# tps62180_v0001.net
KiCad netlist of a schematic drawn in EAGLE
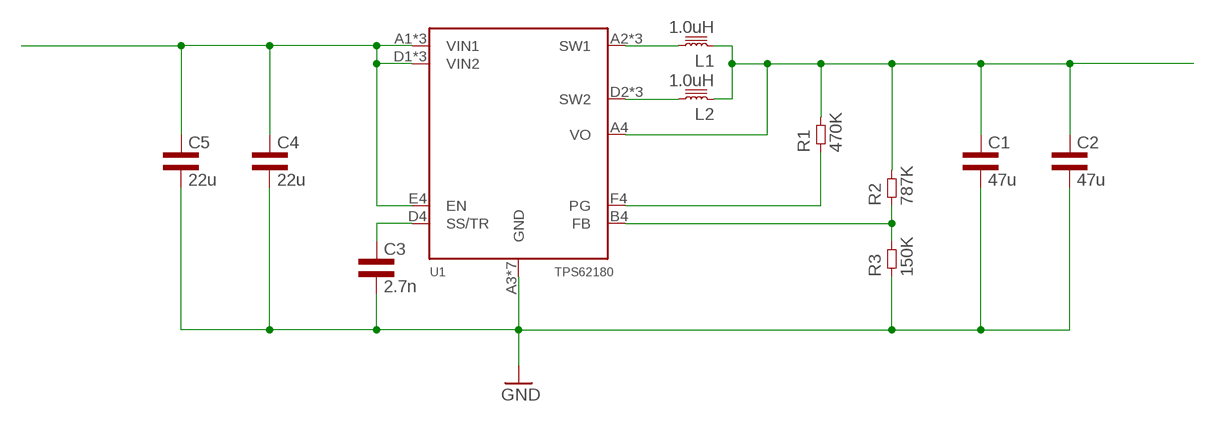
[diagram p0: schematic, sheet 1]

(export (version "E")
  (design (tool "Eeschema 10.0.6"))
  (components
    (comp (ref "C1")
      (value "47u")
      (footprint "eagle-import:1206L3")
      (libsource (lib "eagle-import") (part "CAP1206L3"))
    )
    (comp (ref "C2")
      (value "47u")
      (footprint "eagle-import:1206L3")
      (libsource (lib "eagle-import") (part "CAP1206L3"))
    )
    (comp (ref "C3")
      (value "2.7n")
      (footprint "eagle-import:0402L3")
      (libsource (lib "eagle-import") (part "CAP0402L3"))
    )
    (comp (ref "C4")
      (value "22u")
      (footprint "eagle-import:1206L3")
      (libsource (lib "eagle-import") (part "CAP1206L3"))
    )
    (comp (ref "C5")
      (value "22u")
      (footprint "eagle-import:1206L3")
      (libsource (lib "eagle-import") (part "CAP1206L3"))
    )
    (comp (ref "L1")
      (value "1.0uH")
      (footprint "eagle-import:SPM3012")
      (libsource (lib "eagle-import") (part "INDUCTORSPM3012"))
    )
    (comp (ref "L2")
      (value "1.0uH")
      (footprint "eagle-import:SPM3012")
      (libsource (lib "eagle-import") (part "INDUCTORSPM3012"))
    )
    (comp (ref "R1")
      (value "470K")
      (footprint "eagle-import:0603L3")
      (libsource (lib "eagle-import") (part "RES0603L3"))
    )
    (comp (ref "R2")
      (value "787K")
      (footprint "eagle-import:0603L3")
      (libsource (lib "eagle-import") (part "RES0603L3"))
    )
    (comp (ref "R3")
      (value "150K")
      (footprint "eagle-import:0603L3")
      (libsource (lib "eagle-import") (part "RES0603L3"))
    )
    (comp (ref "U1")
      (value "TPS62180")
      (footprint "eagle-import:R-XBGA-N24")
      (libsource (lib "eagle-import") (part "TPS62180"))
    )
  )
  (nets
    (net (code "1") (name "GND") (class "Default")
      (node (ref "C1") (pin "2") (pinfunction "2_2") (pintype "bidirectional"))
      (node (ref "C2") (pin "2") (pinfunction "2_2") (pintype "bidirectional"))
      (node (ref "C3") (pin "P$2") (pinfunction "2_P$2") (pintype "bidirectional"))
      (node (ref "C4") (pin "2") (pinfunction "2_2") (pintype "bidirectional"))
      (node (ref "C5") (pin "2") (pinfunction "2_2") (pintype "bidirectional"))
      (node (ref "R3") (pin "P$1") (pinfunction "1_P$1") (pintype "bidirectional"))
      (node (ref "U1") (pin "A3") (pinfunction "GND_A3") (pintype "bidirectional"))
      (node (ref "U1") (pin "B3") (pinfunction "GND_B3") (pintype "bidirectional"))
      (node (ref "U1") (pin "C3") (pinfunction "GND_C3") (pintype "bidirectional"))
      (node (ref "U1") (pin "C4") (pinfunction "GND_C4") (pintype "bidirectional"))
      (node (ref "U1") (pin "D3") (pinfunction "GND_D3") (pintype "bidirectional"))
      (node (ref "U1") (pin "E3") (pinfunction "GND_E3") (pintype "bidirectional"))
      (node (ref "U1") (pin "F3") (pinfunction "GND_F3") (pintype "bidirectional"))
    )
    (net (code "2") (name "Net-(C3-1)") (class "Default")
      (node (ref "C3") (pin "P$1") (pinfunction "1_P$1") (pintype "bidirectional"))
      (node (ref "U1") (pin "D4") (pinfunction "SS/TR_D4") (pintype "bidirectional"))
    )
    (net (code "3") (name "Net-(L1-Pad2)") (class "Default")
      (node (ref "L1") (pin "2") (pinfunction "2_2") (pintype "bidirectional"))
      (node (ref "U1") (pin "A2") (pinfunction "SW1_A2") (pintype "bidirectional"))
      (node (ref "U1") (pin "B2") (pinfunction "SW1_B2") (pintype "bidirectional"))
      (node (ref "U1") (pin "C2") (pinfunction "SW1_C2") (pintype "bidirectional"))
    )
    (net (code "4") (name "Net-(L2-Pad2)") (class "Default")
      (node (ref "L2") (pin "2") (pinfunction "2_2") (pintype "bidirectional"))
      (node (ref "U1") (pin "D2") (pinfunction "SW2_D2") (pintype "bidirectional"))
      (node (ref "U1") (pin "E2") (pinfunction "SW2_E2") (pintype "bidirectional"))
      (node (ref "U1") (pin "F2") (pinfunction "SW2_F2") (pintype "bidirectional"))
    )
    (net (code "5") (name "Net-(R1-1)") (class "Default")
      (node (ref "R1") (pin "P$1") (pinfunction "1_P$1") (pintype "bidirectional"))
      (node (ref "U1") (pin "F4") (pinfunction "PG_F4") (pintype "bidirectional"))
    )
    (net (code "6") (name "Net-(R1-2)") (class "Default")
      (node (ref "C1") (pin "1") (pinfunction "1_1") (pintype "bidirectional"))
      (node (ref "C2") (pin "1") (pinfunction "1_1") (pintype "bidirectional"))
      (node (ref "L1") (pin "1") (pinfunction "1_1") (pintype "bidirectional"))
      (node (ref "L2") (pin "1") (pinfunction "1_1") (pintype "bidirectional"))
      (node (ref "R1") (pin "P$2") (pinfunction "2_P$2") (pintype "bidirectional"))
      (node (ref "R2") (pin "P$2") (pinfunction "2_P$2") (pintype "bidirectional"))
      (node (ref "U1") (pin "A4") (pinfunction "VO_A4") (pintype "bidirectional"))
    )
    (net (code "7") (name "Net-(R2-1)") (class "Default")
      (node (ref "R2") (pin "P$1") (pinfunction "1_P$1") (pintype "bidirectional"))
      (node (ref "R3") (pin "P$2") (pinfunction "2_P$2") (pintype "bidirectional"))
      (node (ref "U1") (pin "B4") (pinfunction "FB_B4") (pintype "bidirectional"))
    )
    (net (code "8") (name "Net-(U1-EN)") (class "Default")
      (node (ref "C4") (pin "1") (pinfunction "1_1") (pintype "bidirectional"))
      (node (ref "C5") (pin "1") (pinfunction "1_1") (pintype "bidirectional"))
      (node (ref "U1") (pin "A1") (pinfunction "VIN1_A1") (pintype "bidirectional"))
      (node (ref "U1") (pin "B1") (pinfunction "VIN1_B1") (pintype "bidirectional"))
      (node (ref "U1") (pin "C1") (pinfunction "VIN1_C1") (pintype "bidirectional"))
      (node (ref "U1") (pin "D1") (pinfunction "VIN2_D1") (pintype "bidirectional"))
      (node (ref "U1") (pin "E1") (pinfunction "VIN2_E1") (pintype "bidirectional"))
      (node (ref "U1") (pin "E4") (pinfunction "EN_E4") (pintype "bidirectional"))
      (node (ref "U1") (pin "F1") (pinfunction "VIN2_F1") (pintype "bidirectional"))
    )
  )
)
